# Sche.net
KiCad netlist of a schematic drawn in Altium Designer
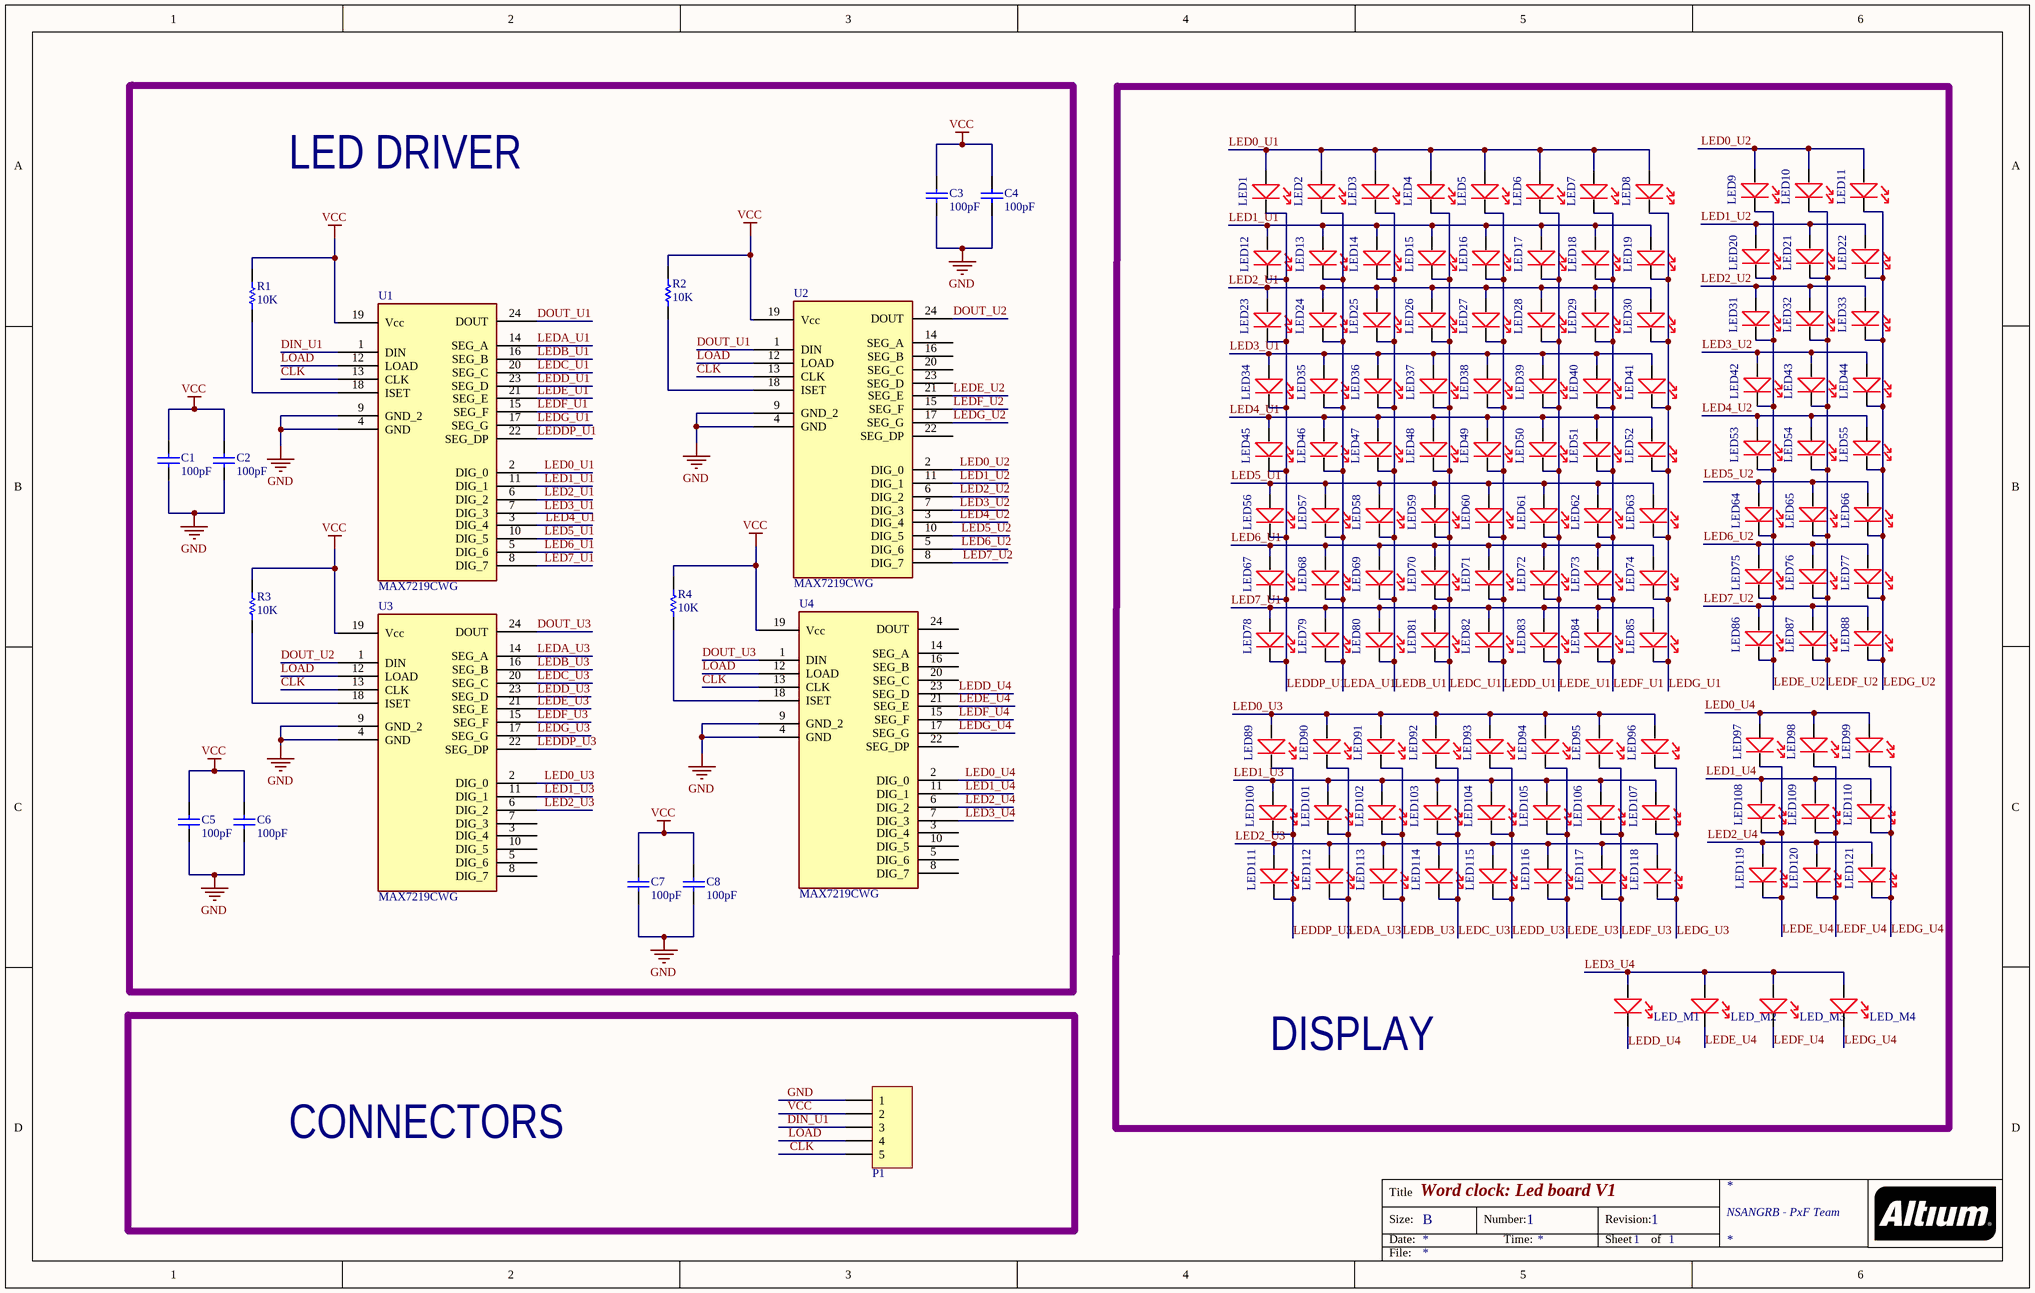
[diagram p0: Sche.SchDoc]

(export (version "E")
  (design (tool "Eeschema 10.0.6"))
  (components
    (comp (ref "C1")
      (value "100pF")
      (footprint "CAP-SM-0805")
      (description "Capacitor")
      (fields (field (name "Comment") "Cap Non-Pol SMD"))
      (libsource (lib "PIF_Library") (part "Cap Non-Pol SMD"))
    )
    (comp (ref "C2")
      (value "100pF")
      (footprint "CAP-SM-0805")
      (description "Capacitor")
      (fields (field (name "Comment") "Cap Non-Pol SMD"))
      (libsource (lib "PIF_Library") (part "Cap Non-Pol SMD"))
    )
    (comp (ref "C3")
      (value "100pF")
      (footprint "CAP-SM-0805")
      (description "Capacitor")
      (fields (field (name "Comment") "Cap Non-Pol SMD"))
      (libsource (lib "PIF_Library") (part "Cap Non-Pol SMD"))
    )
    (comp (ref "C4")
      (value "100pF")
      (footprint "CAP-SM-0805")
      (description "Capacitor")
      (fields (field (name "Comment") "Cap Non-Pol SMD"))
      (libsource (lib "PIF_Library") (part "Cap Non-Pol SMD"))
    )
    (comp (ref "C5")
      (value "100pF")
      (footprint "CAP-SM-0805")
      (description "Capacitor")
      (fields (field (name "Comment") "Cap Non-Pol SMD"))
      (libsource (lib "PIF_Library") (part "Cap Non-Pol SMD"))
    )
    (comp (ref "C6")
      (value "100pF")
      (footprint "CAP-SM-0805")
      (description "Capacitor")
      (fields (field (name "Comment") "Cap Non-Pol SMD"))
      (libsource (lib "PIF_Library") (part "Cap Non-Pol SMD"))
    )
    (comp (ref "C7")
      (value "100pF")
      (footprint "CAP-SM-0805")
      (description "Capacitor")
      (fields (field (name "Comment") "Cap Non-Pol SMD"))
      (libsource (lib "PIF_Library") (part "Cap Non-Pol SMD"))
    )
    (comp (ref "C8")
      (value "100pF")
      (footprint "CAP-SM-0805")
      (description "Capacitor")
      (fields (field (name "Comment") "Cap Non-Pol SMD"))
      (libsource (lib "PIF_Library") (part "Cap Non-Pol SMD"))
    )
    (comp (ref "LED1")
      (value "KA-3528EC")
      (footprint "DIOM3020X13N")
      (description "KINGBRIGHT         KA-3528EC             LED, Red, SMD, 2.4mm, 20 mA, 2 V, 627 nm")
      (fields (field (name "MANUFACTURER") "Kingbright"))
      (libsource (lib "WC_Lib") (part "LED_3528"))
    )
    (comp (ref "LED2")
      (value "KA-3528EC")
      (footprint "DIOM3020X13N")
      (description "KINGBRIGHT         KA-3528EC             LED, Red, SMD, 2.4mm, 20 mA, 2 V, 627 nm")
      (fields (field (name "MANUFACTURER") "Kingbright"))
      (libsource (lib "WC_Lib") (part "LED_3528"))
    )
    (comp (ref "LED3")
      (value "KA-3528EC")
      (footprint "DIOM3020X13N")
      (description "KINGBRIGHT         KA-3528EC             LED, Red, SMD, 2.4mm, 20 mA, 2 V, 627 nm")
      (fields (field (name "MANUFACTURER") "Kingbright"))
      (libsource (lib "WC_Lib") (part "LED_3528"))
    )
    (comp (ref "LED4")
      (value "KA-3528EC")
      (footprint "DIOM3020X13N")
      (description "KINGBRIGHT         KA-3528EC             LED, Red, SMD, 2.4mm, 20 mA, 2 V, 627 nm")
      (fields (field (name "MANUFACTURER") "Kingbright"))
      (libsource (lib "WC_Lib") (part "LED_3528"))
    )
    (comp (ref "LED5")
      (value "KA-3528EC")
      (footprint "DIOM3020X13N")
      (description "KINGBRIGHT         KA-3528EC             LED, Red, SMD, 2.4mm, 20 mA, 2 V, 627 nm")
      (fields (field (name "MANUFACTURER") "Kingbright"))
      (libsource (lib "WC_Lib") (part "LED_3528"))
    )
    (comp (ref "LED6")
      (value "KA-3528EC")
      (footprint "DIOM3020X13N")
      (description "KINGBRIGHT         KA-3528EC             LED, Red, SMD, 2.4mm, 20 mA, 2 V, 627 nm")
      (fields (field (name "MANUFACTURER") "Kingbright"))
      (libsource (lib "WC_Lib") (part "LED_3528"))
    )
    (comp (ref "LED7")
      (value "KA-3528EC")
      (footprint "DIOM3020X13N")
      (description "KINGBRIGHT         KA-3528EC             LED, Red, SMD, 2.4mm, 20 mA, 2 V, 627 nm")
      (fields (field (name "MANUFACTURER") "Kingbright"))
      (libsource (lib "WC_Lib") (part "LED_3528"))
    )
    (comp (ref "LED8")
      (value "KA-3528EC")
      (footprint "DIOM3020X13N")
      (description "KINGBRIGHT         KA-3528EC             LED, Red, SMD, 2.4mm, 20 mA, 2 V, 627 nm")
      (fields (field (name "MANUFACTURER") "Kingbright"))
      (libsource (lib "WC_Lib") (part "LED_3528"))
    )
    (comp (ref "LED9")
      (value "KA-3528EC")
      (footprint "DIOM3020X13N")
      (description "KINGBRIGHT         KA-3528EC             LED, Red, SMD, 2.4mm, 20 mA, 2 V, 627 nm")
      (fields (field (name "MANUFACTURER") "Kingbright"))
      (libsource (lib "WC_Lib") (part "LED_3528"))
    )
    (comp (ref "LED10")
      (value "KA-3528EC")
      (footprint "DIOM3020X13N")
      (description "KINGBRIGHT         KA-3528EC             LED, Red, SMD, 2.4mm, 20 mA, 2 V, 627 nm")
      (fields (field (name "MANUFACTURER") "Kingbright"))
      (libsource (lib "WC_Lib") (part "LED_3528"))
    )
    (comp (ref "LED11")
      (value "KA-3528EC")
      (footprint "DIOM3020X13N")
      (description "KINGBRIGHT         KA-3528EC             LED, Red, SMD, 2.4mm, 20 mA, 2 V, 627 nm")
      (fields (field (name "MANUFACTURER") "Kingbright"))
      (libsource (lib "WC_Lib") (part "LED_3528"))
    )
    (comp (ref "LED12")
      (value "KA-3528EC")
      (footprint "DIOM3020X13N")
      (description "KINGBRIGHT         KA-3528EC             LED, Red, SMD, 2.4mm, 20 mA, 2 V, 627 nm")
      (fields (field (name "MANUFACTURER") "Kingbright"))
      (libsource (lib "WC_Lib") (part "LED_3528"))
    )
    (comp (ref "LED13")
      (value "KA-3528EC")
      (footprint "DIOM3020X13N")
      (description "KINGBRIGHT         KA-3528EC             LED, Red, SMD, 2.4mm, 20 mA, 2 V, 627 nm")
      (fields (field (name "MANUFACTURER") "Kingbright"))
      (libsource (lib "WC_Lib") (part "LED_3528"))
    )
    (comp (ref "LED14")
      (value "KA-3528EC")
      (footprint "DIOM3020X13N")
      (description "KINGBRIGHT         KA-3528EC             LED, Red, SMD, 2.4mm, 20 mA, 2 V, 627 nm")
      (fields (field (name "MANUFACTURER") "Kingbright"))
      (libsource (lib "WC_Lib") (part "LED_3528"))
    )
    (comp (ref "LED15")
      (value "KA-3528EC")
      (footprint "DIOM3020X13N")
      (description "KINGBRIGHT         KA-3528EC             LED, Red, SMD, 2.4mm, 20 mA, 2 V, 627 nm")
      (fields (field (name "MANUFACTURER") "Kingbright"))
      (libsource (lib "WC_Lib") (part "LED_3528"))
    )
    (comp (ref "LED16")
      (value "KA-3528EC")
      (footprint "DIOM3020X13N")
      (description "KINGBRIGHT         KA-3528EC             LED, Red, SMD, 2.4mm, 20 mA, 2 V, 627 nm")
      (fields (field (name "MANUFACTURER") "Kingbright"))
      (libsource (lib "WC_Lib") (part "LED_3528"))
    )
    (comp (ref "LED17")
      (value "KA-3528EC")
      (footprint "DIOM3020X13N")
      (description "KINGBRIGHT         KA-3528EC             LED, Red, SMD, 2.4mm, 20 mA, 2 V, 627 nm")
      (fields (field (name "MANUFACTURER") "Kingbright"))
      (libsource (lib "WC_Lib") (part "LED_3528"))
    )
    (comp (ref "LED18")
      (value "KA-3528EC")
      (footprint "DIOM3020X13N")
      (description "KINGBRIGHT         KA-3528EC             LED, Red, SMD, 2.4mm, 20 mA, 2 V, 627 nm")
      (fields (field (name "MANUFACTURER") "Kingbright"))
      (libsource (lib "WC_Lib") (part "LED_3528"))
    )
    (comp (ref "LED19")
      (value "KA-3528EC")
      (footprint "DIOM3020X13N")
      (description "KINGBRIGHT         KA-3528EC             LED, Red, SMD, 2.4mm, 20 mA, 2 V, 627 nm")
      (fields (field (name "MANUFACTURER") "Kingbright"))
      (libsource (lib "WC_Lib") (part "LED_3528"))
    )
    (comp (ref "LED20")
      (value "KA-3528EC")
      (footprint "DIOM3020X13N")
      (description "KINGBRIGHT         KA-3528EC             LED, Red, SMD, 2.4mm, 20 mA, 2 V, 627 nm")
      (fields (field (name "MANUFACTURER") "Kingbright"))
      (libsource (lib "WC_Lib") (part "LED_3528"))
    )
    (comp (ref "LED21")
      (value "KA-3528EC")
      (footprint "DIOM3020X13N")
      (description "KINGBRIGHT         KA-3528EC             LED, Red, SMD, 2.4mm, 20 mA, 2 V, 627 nm")
      (fields (field (name "MANUFACTURER") "Kingbright"))
      (libsource (lib "WC_Lib") (part "LED_3528"))
    )
    (comp (ref "LED22")
      (value "KA-3528EC")
      (footprint "DIOM3020X13N")
      (description "KINGBRIGHT         KA-3528EC             LED, Red, SMD, 2.4mm, 20 mA, 2 V, 627 nm")
      (fields (field (name "MANUFACTURER") "Kingbright"))
      (libsource (lib "WC_Lib") (part "LED_3528"))
    )
    (comp (ref "LED23")
      (value "KA-3528EC")
      (footprint "DIOM3020X13N")
      (description "KINGBRIGHT         KA-3528EC             LED, Red, SMD, 2.4mm, 20 mA, 2 V, 627 nm")
      (fields (field (name "MANUFACTURER") "Kingbright"))
      (libsource (lib "WC_Lib") (part "LED_3528"))
    )
    (comp (ref "LED24")
      (value "KA-3528EC")
      (footprint "DIOM3020X13N")
      (description "KINGBRIGHT         KA-3528EC             LED, Red, SMD, 2.4mm, 20 mA, 2 V, 627 nm")
      (fields (field (name "MANUFACTURER") "Kingbright"))
      (libsource (lib "WC_Lib") (part "LED_3528"))
    )
    (comp (ref "LED25")
      (value "KA-3528EC")
      (footprint "DIOM3020X13N")
      (description "KINGBRIGHT         KA-3528EC             LED, Red, SMD, 2.4mm, 20 mA, 2 V, 627 nm")
      (fields (field (name "MANUFACTURER") "Kingbright"))
      (libsource (lib "WC_Lib") (part "LED_3528"))
    )
    (comp (ref "LED26")
      (value "KA-3528EC")
      (footprint "DIOM3020X13N")
      (description "KINGBRIGHT         KA-3528EC             LED, Red, SMD, 2.4mm, 20 mA, 2 V, 627 nm")
      (fields (field (name "MANUFACTURER") "Kingbright"))
      (libsource (lib "WC_Lib") (part "LED_3528"))
    )
    (comp (ref "LED27")
      (value "KA-3528EC")
      (footprint "DIOM3020X13N")
      (description "KINGBRIGHT         KA-3528EC             LED, Red, SMD, 2.4mm, 20 mA, 2 V, 627 nm")
      (fields (field (name "MANUFACTURER") "Kingbright"))
      (libsource (lib "WC_Lib") (part "LED_3528"))
    )
    (comp (ref "LED28")
      (value "KA-3528EC")
      (footprint "DIOM3020X13N")
      (description "KINGBRIGHT         KA-3528EC             LED, Red, SMD, 2.4mm, 20 mA, 2 V, 627 nm")
      (fields (field (name "MANUFACTURER") "Kingbright"))
      (libsource (lib "WC_Lib") (part "LED_3528"))
    )
    (comp (ref "LED29")
      (value "KA-3528EC")
      (footprint "DIOM3020X13N")
      (description "KINGBRIGHT         KA-3528EC             LED, Red, SMD, 2.4mm, 20 mA, 2 V, 627 nm")
      (fields (field (name "MANUFACTURER") "Kingbright"))
      (libsource (lib "WC_Lib") (part "LED_3528"))
    )
    (comp (ref "LED30")
      (value "KA-3528EC")
      (footprint "DIOM3020X13N")
      (description "KINGBRIGHT         KA-3528EC             LED, Red, SMD, 2.4mm, 20 mA, 2 V, 627 nm")
      (fields (field (name "MANUFACTURER") "Kingbright"))
      (libsource (lib "WC_Lib") (part "LED_3528"))
    )
    (comp (ref "LED31")
      (value "KA-3528EC")
      (footprint "DIOM3020X13N")
      (description "KINGBRIGHT         KA-3528EC             LED, Red, SMD, 2.4mm, 20 mA, 2 V, 627 nm")
      (fields (field (name "MANUFACTURER") "Kingbright"))
      (libsource (lib "WC_Lib") (part "LED_3528"))
    )
    (comp (ref "LED32")
      (value "KA-3528EC")
      (footprint "DIOM3020X13N")
      (description "KINGBRIGHT         KA-3528EC             LED, Red, SMD, 2.4mm, 20 mA, 2 V, 627 nm")
      (fields (field (name "MANUFACTURER") "Kingbright"))
      (libsource (lib "WC_Lib") (part "LED_3528"))
    )
    (comp (ref "LED33")
      (value "KA-3528EC")
      (footprint "DIOM3020X13N")
      (description "KINGBRIGHT         KA-3528EC             LED, Red, SMD, 2.4mm, 20 mA, 2 V, 627 nm")
      (fields (field (name "MANUFACTURER") "Kingbright"))
      (libsource (lib "WC_Lib") (part "LED_3528"))
    )
    (comp (ref "LED34")
      (value "KA-3528EC")
      (footprint "DIOM3020X13N")
      (description "KINGBRIGHT         KA-3528EC             LED, Red, SMD, 2.4mm, 20 mA, 2 V, 627 nm")
      (fields (field (name "MANUFACTURER") "Kingbright"))
      (libsource (lib "WC_Lib") (part "LED_3528"))
    )
    (comp (ref "LED35")
      (value "KA-3528EC")
      (footprint "DIOM3020X13N")
      (description "KINGBRIGHT         KA-3528EC             LED, Red, SMD, 2.4mm, 20 mA, 2 V, 627 nm")
      (fields (field (name "MANUFACTURER") "Kingbright"))
      (libsource (lib "WC_Lib") (part "LED_3528"))
    )
    (comp (ref "LED36")
      (value "KA-3528EC")
      (footprint "DIOM3020X13N")
      (description "KINGBRIGHT         KA-3528EC             LED, Red, SMD, 2.4mm, 20 mA, 2 V, 627 nm")
      (fields (field (name "MANUFACTURER") "Kingbright"))
      (libsource (lib "WC_Lib") (part "LED_3528"))
    )
    (comp (ref "LED37")
      (value "KA-3528EC")
      (footprint "DIOM3020X13N")
      (description "KINGBRIGHT         KA-3528EC             LED, Red, SMD, 2.4mm, 20 mA, 2 V, 627 nm")
      (fields (field (name "MANUFACTURER") "Kingbright"))
      (libsource (lib "WC_Lib") (part "LED_3528"))
    )
    (comp (ref "LED38")
      (value "KA-3528EC")
      (footprint "DIOM3020X13N")
      (description "KINGBRIGHT         KA-3528EC             LED, Red, SMD, 2.4mm, 20 mA, 2 V, 627 nm")
      (fields (field (name "MANUFACTURER") "Kingbright"))
      (libsource (lib "WC_Lib") (part "LED_3528"))
    )
    (comp (ref "LED39")
      (value "KA-3528EC")
      (footprint "DIOM3020X13N")
      (description "KINGBRIGHT         KA-3528EC             LED, Red, SMD, 2.4mm, 20 mA, 2 V, 627 nm")
      (fields (field (name "MANUFACTURER") "Kingbright"))
      (libsource (lib "WC_Lib") (part "LED_3528"))
    )
    (comp (ref "LED40")
      (value "KA-3528EC")
      (footprint "DIOM3020X13N")
      (description "KINGBRIGHT         KA-3528EC             LED, Red, SMD, 2.4mm, 20 mA, 2 V, 627 nm")
      (fields (field (name "MANUFACTURER") "Kingbright"))
      (libsource (lib "WC_Lib") (part "LED_3528"))
    )
    (comp (ref "LED41")
      (value "KA-3528EC")
      (footprint "DIOM3020X13N")
      (description "KINGBRIGHT         KA-3528EC             LED, Red, SMD, 2.4mm, 20 mA, 2 V, 627 nm")
      (fields (field (name "MANUFACTURER") "Kingbright"))
      (libsource (lib "WC_Lib") (part "LED_3528"))
    )
    (comp (ref "LED42")
      (value "KA-3528EC")
      (footprint "DIOM3020X13N")
      (description "KINGBRIGHT         KA-3528EC             LED, Red, SMD, 2.4mm, 20 mA, 2 V, 627 nm")
      (fields (field (name "MANUFACTURER") "Kingbright"))
      (libsource (lib "WC_Lib") (part "LED_3528"))
    )
    (comp (ref "LED43")
      (value "KA-3528EC")
      (footprint "DIOM3020X13N")
      (description "KINGBRIGHT         KA-3528EC             LED, Red, SMD, 2.4mm, 20 mA, 2 V, 627 nm")
      (fields (field (name "MANUFACTURER") "Kingbright"))
      (libsource (lib "WC_Lib") (part "LED_3528"))
    )
    (comp (ref "LED44")
      (value "KA-3528EC")
      (footprint "DIOM3020X13N")
      (description "KINGBRIGHT         KA-3528EC             LED, Red, SMD, 2.4mm, 20 mA, 2 V, 627 nm")
      (fields (field (name "MANUFACTURER") "Kingbright"))
      (libsource (lib "WC_Lib") (part "LED_3528"))
    )
    (comp (ref "LED45")
      (value "KA-3528EC")
      (footprint "DIOM3020X13N")
      (description "KINGBRIGHT         KA-3528EC             LED, Red, SMD, 2.4mm, 20 mA, 2 V, 627 nm")
      (fields (field (name "MANUFACTURER") "Kingbright"))
      (libsource (lib "WC_Lib") (part "LED_3528"))
    )
    (comp (ref "LED46")
      (value "KA-3528EC")
      (footprint "DIOM3020X13N")
      (description "KINGBRIGHT         KA-3528EC             LED, Red, SMD, 2.4mm, 20 mA, 2 V, 627 nm")
      (fields (field (name "MANUFACTURER") "Kingbright"))
      (libsource (lib "WC_Lib") (part "LED_3528"))
    )
    (comp (ref "LED47")
      (value "KA-3528EC")
      (footprint "DIOM3020X13N")
      (description "KINGBRIGHT         KA-3528EC             LED, Red, SMD, 2.4mm, 20 mA, 2 V, 627 nm")
      (fields (field (name "MANUFACTURER") "Kingbright"))
      (libsource (lib "WC_Lib") (part "LED_3528"))
    )
    (comp (ref "LED48")
      (value "KA-3528EC")
      (footprint "DIOM3020X13N")
      (description "KINGBRIGHT         KA-3528EC             LED, Red, SMD, 2.4mm, 20 mA, 2 V, 627 nm")
      (fields (field (name "MANUFACTURER") "Kingbright"))
      (libsource (lib "WC_Lib") (part "LED_3528"))
    )
    (comp (ref "LED49")
      (value "KA-3528EC")
      (footprint "DIOM3020X13N")
      (description "KINGBRIGHT         KA-3528EC             LED, Red, SMD, 2.4mm, 20 mA, 2 V, 627 nm")
      (fields (field (name "MANUFACTURER") "Kingbright"))
      (libsource (lib "WC_Lib") (part "LED_3528"))
    )
    (comp (ref "LED50")
      (value "KA-3528EC")
      (footprint "DIOM3020X13N")
      (description "KINGBRIGHT         KA-3528EC             LED, Red, SMD, 2.4mm, 20 mA, 2 V, 627 nm")
      (fields (field (name "MANUFACTURER") "Kingbright"))
      (libsource (lib "WC_Lib") (part "LED_3528"))
    )
    (comp (ref "LED51")
      (value "KA-3528EC")
      (footprint "DIOM3020X13N")
      (description "KINGBRIGHT         KA-3528EC             LED, Red, SMD, 2.4mm, 20 mA, 2 V, 627 nm")
      (fields (field (name "MANUFACTURER") "Kingbright"))
      (libsource (lib "WC_Lib") (part "LED_3528"))
    )
    (comp (ref "LED52")
      (value "KA-3528EC")
      (footprint "DIOM3020X13N")
      (description "KINGBRIGHT         KA-3528EC             LED, Red, SMD, 2.4mm, 20 mA, 2 V, 627 nm")
      (fields (field (name "MANUFACTURER") "Kingbright"))
      (libsource (lib "WC_Lib") (part "LED_3528"))
    )
    (comp (ref "LED53")
      (value "KA-3528EC")
      (footprint "DIOM3020X13N")
      (description "KINGBRIGHT         KA-3528EC             LED, Red, SMD, 2.4mm, 20 mA, 2 V, 627 nm")
      (fields (field (name "MANUFACTURER") "Kingbright"))
      (libsource (lib "WC_Lib") (part "LED_3528"))
    )
    (comp (ref "LED54")
      (value "KA-3528EC")
      (footprint "DIOM3020X13N")
      (description "KINGBRIGHT         KA-3528EC             LED, Red, SMD, 2.4mm, 20 mA, 2 V, 627 nm")
      (fields (field (name "MANUFACTURER") "Kingbright"))
      (libsource (lib "WC_Lib") (part "LED_3528"))
    )
    (comp (ref "LED55")
      (value "KA-3528EC")
      (footprint "DIOM3020X13N")
      (description "KINGBRIGHT         KA-3528EC             LED, Red, SMD, 2.4mm, 20 mA, 2 V, 627 nm")
      (fields (field (name "MANUFACTURER") "Kingbright"))
      (libsource (lib "WC_Lib") (part "LED_3528"))
    )
    (comp (ref "LED56")
      (value "KA-3528EC")
      (footprint "DIOM3020X13N")
      (description "KINGBRIGHT         KA-3528EC             LED, Red, SMD, 2.4mm, 20 mA, 2 V, 627 nm")
      (fields (field (name "MANUFACTURER") "Kingbright"))
      (libsource (lib "WC_Lib") (part "LED_3528"))
    )
    (comp (ref "LED57")
      (value "KA-3528EC")
      (footprint "DIOM3020X13N")
      (description "KINGBRIGHT         KA-3528EC             LED, Red, SMD, 2.4mm, 20 mA, 2 V, 627 nm")
      (fields (field (name "MANUFACTURER") "Kingbright"))
      (libsource (lib "WC_Lib") (part "LED_3528"))
    )
    (comp (ref "LED58")
      (value "KA-3528EC")
      (footprint "DIOM3020X13N")
      (description "KINGBRIGHT         KA-3528EC             LED, Red, SMD, 2.4mm, 20 mA, 2 V, 627 nm")
      (fields (field (name "MANUFACTURER") "Kingbright"))
      (libsource (lib "WC_Lib") (part "LED_3528"))
    )
    (comp (ref "LED59")
      (value "KA-3528EC")
      (footprint "DIOM3020X13N")
      (description "KINGBRIGHT         KA-3528EC             LED, Red, SMD, 2.4mm, 20 mA, 2 V, 627 nm")
      (fields (field (name "MANUFACTURER") "Kingbright"))
      (libsource (lib "WC_Lib") (part "LED_3528"))
    )
    (comp (ref "LED60")
      (value "KA-3528EC")
      (footprint "DIOM3020X13N")
      (description "KINGBRIGHT         KA-3528EC             LED, Red, SMD, 2.4mm, 20 mA, 2 V, 627 nm")
      (fields (field (name "MANUFACTURER") "Kingbright"))
      (libsource (lib "WC_Lib") (part "LED_3528"))
    )
    (comp (ref "LED61")
      (value "KA-3528EC")
      (footprint "DIOM3020X13N")
      (description "KINGBRIGHT         KA-3528EC             LED, Red, SMD, 2.4mm, 20 mA, 2 V, 627 nm")
      (fields (field (name "MANUFACTURER") "Kingbright"))
      (libsource (lib "WC_Lib") (part "LED_3528"))
    )
    (comp (ref "LED62")
      (value "KA-3528EC")
      (footprint "DIOM3020X13N")
      (description "KINGBRIGHT         KA-3528EC             LED, Red, SMD, 2.4mm, 20 mA, 2 V, 627 nm")
      (fields (field (name "MANUFACTURER") "Kingbright"))
      (libsource (lib "WC_Lib") (part "LED_3528"))
    )
    (comp (ref "LED63")
      (value "KA-3528EC")
      (footprint "DIOM3020X13N")
      (description "KINGBRIGHT         KA-3528EC             LED, Red, SMD, 2.4mm, 20 mA, 2 V, 627 nm")
      (fields (field (name "MANUFACTURER") "Kingbright"))
      (libsource (lib "WC_Lib") (part "LED_3528"))
    )
    (comp (ref "LED64")
      (value "KA-3528EC")
      (footprint "DIOM3020X13N")
      (description "KINGBRIGHT         KA-3528EC             LED, Red, SMD, 2.4mm, 20 mA, 2 V, 627 nm")
      (fields (field (name "MANUFACTURER") "Kingbright"))
      (libsource (lib "WC_Lib") (part "LED_3528"))
    )
    (comp (ref "LED65")
      (value "KA-3528EC")
      (footprint "DIOM3020X13N")
      (description "KINGBRIGHT         KA-3528EC             LED, Red, SMD, 2.4mm, 20 mA, 2 V, 627 nm")
      (fields (field (name "MANUFACTURER") "Kingbright"))
      (libsource (lib "WC_Lib") (part "LED_3528"))
    )
    (comp (ref "LED66")
      (value "KA-3528EC")
      (footprint "DIOM3020X13N")
      (description "KINGBRIGHT         KA-3528EC             LED, Red, SMD, 2.4mm, 20 mA, 2 V, 627 nm")
      (fields (field (name "MANUFACTURER") "Kingbright"))
      (libsource (lib "WC_Lib") (part "LED_3528"))
    )
    (comp (ref "LED67")
      (value "KA-3528EC")
      (footprint "DIOM3020X13N")
      (description "KINGBRIGHT         KA-3528EC             LED, Red, SMD, 2.4mm, 20 mA, 2 V, 627 nm")
      (fields (field (name "MANUFACTURER") "Kingbright"))
      (libsource (lib "WC_Lib") (part "LED_3528"))
    )
    (comp (ref "LED68")
      (value "KA-3528EC")
      (footprint "DIOM3020X13N")
      (description "KINGBRIGHT         KA-3528EC             LED, Red, SMD, 2.4mm, 20 mA, 2 V, 627 nm")
      (fields (field (name "MANUFACTURER") "Kingbright"))
      (libsource (lib "WC_Lib") (part "LED_3528"))
    )
    (comp (ref "LED69")
      (value "KA-3528EC")
      (footprint "DIOM3020X13N")
      (description "KINGBRIGHT         KA-3528EC             LED, Red, SMD, 2.4mm, 20 mA, 2 V, 627 nm")
      (fields (field (name "MANUFACTURER") "Kingbright"))
      (libsource (lib "WC_Lib") (part "LED_3528"))
    )
    (comp (ref "LED70")
      (value "KA-3528EC")
      (footprint "DIOM3020X13N")
      (description "KINGBRIGHT         KA-3528EC             LED, Red, SMD, 2.4mm, 20 mA, 2 V, 627 nm")
      (fields (field (name "MANUFACTURER") "Kingbright"))
      (libsource (lib "WC_Lib") (part "LED_3528"))
    )
    (comp (ref "LED71")
      (value "KA-3528EC")
      (footprint "DIOM3020X13N")
      (description "KINGBRIGHT         KA-3528EC             LED, Red, SMD, 2.4mm, 20 mA, 2 V, 627 nm")
      (fields (field (name "MANUFACTURER") "Kingbright"))
      (libsource (lib "WC_Lib") (part "LED_3528"))
    )
    (comp (ref "LED72")
      (value "KA-3528EC")
      (footprint "DIOM3020X13N")
      (description "KINGBRIGHT         KA-3528EC             LED, Red, SMD, 2.4mm, 20 mA, 2 V, 627 nm")
      (fields (field (name "MANUFACTURER") "Kingbright"))
      (libsource (lib "WC_Lib") (part "LED_3528"))
    )
    (comp (ref "LED73")
      (value "KA-3528EC")
      (footprint "DIOM3020X13N")
      (description "KINGBRIGHT         KA-3528EC             LED, Red, SMD, 2.4mm, 20 mA, 2 V, 627 nm")
      (fields (field (name "MANUFACTURER") "Kingbright"))
      (libsource (lib "WC_Lib") (part "LED_3528"))
    )
    (comp (ref "LED74")
      (value "KA-3528EC")
      (footprint "DIOM3020X13N")
      (description "KINGBRIGHT         KA-3528EC             LED, Red, SMD, 2.4mm, 20 mA, 2 V, 627 nm")
      (fields (field (name "MANUFACTURER") "Kingbright"))
      (libsource (lib "WC_Lib") (part "LED_3528"))
    )
    (comp (ref "LED75")
      (value "KA-3528EC")
      (footprint "DIOM3020X13N")
      (description "KINGBRIGHT         KA-3528EC             LED, Red, SMD, 2.4mm, 20 mA, 2 V, 627 nm")
      (fields (field (name "MANUFACTURER") "Kingbright"))
      (libsource (lib "WC_Lib") (part "LED_3528"))
    )
    (comp (ref "LED76")
      (value "KA-3528EC")
      (footprint "DIOM3020X13N")
      (description "KINGBRIGHT         KA-3528EC             LED, Red, SMD, 2.4mm, 20 mA, 2 V, 627 nm")
      (fields (field (name "MANUFACTURER") "Kingbright"))
      (libsource (lib "WC_Lib") (part "LED_3528"))
    )
    (comp (ref "LED77")
      (value "KA-3528EC")
      (footprint "DIOM3020X13N")
      (description "KINGBRIGHT         KA-3528EC             LED, Red, SMD, 2.4mm, 20 mA, 2 V, 627 nm")
      (fields (field (name "MANUFACTURER") "Kingbright"))
      (libsource (lib "WC_Lib") (part "LED_3528"))
    )
    (comp (ref "LED78")
      (value "KA-3528EC")
      (footprint "DIOM3020X13N")
      (description "KINGBRIGHT         KA-3528EC             LED, Red, SMD, 2.4mm, 20 mA, 2 V, 627 nm")
      (fields (field (name "MANUFACTURER") "Kingbright"))
      (libsource (lib "WC_Lib") (part "LED_3528"))
    )
    (comp (ref "LED79")
      (value "KA-3528EC")
      (footprint "DIOM3020X13N")
      (description "KINGBRIGHT         KA-3528EC             LED, Red, SMD, 2.4mm, 20 mA, 2 V, 627 nm")
      (fields (field (name "MANUFACTURER") "Kingbright"))
      (libsource (lib "WC_Lib") (part "LED_3528"))
    )
    (comp (ref "LED80")
      (value "KA-3528EC")
      (footprint "DIOM3020X13N")
      (description "KINGBRIGHT         KA-3528EC             LED, Red, SMD, 2.4mm, 20 mA, 2 V, 627 nm")
      (fields (field (name "MANUFACTURER") "Kingbright"))
      (libsource (lib "WC_Lib") (part "LED_3528"))
    )
    (comp (ref "LED81")
      (value "KA-3528EC")
      (footprint "DIOM3020X13N")
      (description "KINGBRIGHT         KA-3528EC             LED, Red, SMD, 2.4mm, 20 mA, 2 V, 627 nm")
      (fields (field (name "MANUFACTURER") "Kingbright"))
      (libsource (lib "WC_Lib") (part "LED_3528"))
    )
    (comp (ref "LED82")
      (value "KA-3528EC")
      (footprint "DIOM3020X13N")
      (description "KINGBRIGHT         KA-3528EC             LED, Red, SMD, 2.4mm, 20 mA, 2 V, 627 nm")
      (fields (field (name "MANUFACTURER") "Kingbright"))
      (libsource (lib "WC_Lib") (part "LED_3528"))
    )
    (comp (ref "LED83")
      (value "KA-3528EC")
      (footprint "DIOM3020X13N")
      (description "KINGBRIGHT         KA-3528EC             LED, Red, SMD, 2.4mm, 20 mA, 2 V, 627 nm")
      (fields (field (name "MANUFACTURER") "Kingbright"))
      (libsource (lib "WC_Lib") (part "LED_3528"))
    )
    (comp (ref "LED84")
      (value "KA-3528EC")
      (footprint "DIOM3020X13N")
      (description "KINGBRIGHT         KA-3528EC             LED, Red, SMD, 2.4mm, 20 mA, 2 V, 627 nm")
      (fields (field (name "MANUFACTURER") "Kingbright"))
      (libsource (lib "WC_Lib") (part "LED_3528"))
    )
    (comp (ref "LED85")
      (value "KA-3528EC")
      (footprint "DIOM3020X13N")
      (description "KINGBRIGHT         KA-3528EC             LED, Red, SMD, 2.4mm, 20 mA, 2 V, 627 nm")
      (fields (field (name "MANUFACTURER") "Kingbright"))
      (libsource (lib "WC_Lib") (part "LED_3528"))
    )
    (comp (ref "LED86")
      (value "KA-3528EC")
      (footprint "DIOM3020X13N")
      (description "KINGBRIGHT         KA-3528EC             LED, Red, SMD, 2.4mm, 20 mA, 2 V, 627 nm")
      (fields (field (name "MANUFACTURER") "Kingbright"))
      (libsource (lib "WC_Lib") (part "LED_3528"))
    )
    (comp (ref "LED87")
      (value "KA-3528EC")
      (footprint "DIOM3020X13N")
      (description "KINGBRIGHT         KA-3528EC             LED, Red, SMD, 2.4mm, 20 mA, 2 V, 627 nm")
      (fields (field (name "MANUFACTURER") "Kingbright"))
      (libsource (lib "WC_Lib") (part "LED_3528"))
    )
    (comp (ref "LED88")
      (value "KA-3528EC")
      (footprint "DIOM3020X13N")
      (description "KINGBRIGHT         KA-3528EC             LED, Red, SMD, 2.4mm, 20 mA, 2 V, 627 nm")
      (fields (field (name "MANUFACTURER") "Kingbright"))
      (libsource (lib "WC_Lib") (part "LED_3528"))
    )
    (comp (ref "LED89")
      (value "KA-3528EC")
      (footprint "DIOM3020X13N")
      (description "KINGBRIGHT         KA-3528EC             LED, Red, SMD, 2.4mm, 20 mA, 2 V, 627 nm")
      (fields (field (name "MANUFACTURER") "Kingbright"))
      (libsource (lib "WC_Lib") (part "LED_3528"))
    )
    (comp (ref "LED90")
      (value "KA-3528EC")
      (footprint "DIOM3020X13N")
      (description "KINGBRIGHT         KA-3528EC             LED, Red, SMD, 2.4mm, 20 mA, 2 V, 627 nm")
      (fields (field (name "MANUFACTURER") "Kingbright"))
      (libsource (lib "WC_Lib") (part "LED_3528"))
    )
    (comp (ref "LED91")
      (value "KA-3528EC")
      (footprint "DIOM3020X13N")
      (description "KINGBRIGHT         KA-3528EC             LED, Red, SMD, 2.4mm, 20 mA, 2 V, 627 nm")
      (fields (field (name "MANUFACTURER") "Kingbright"))
      (libsource (lib "WC_Lib") (part "LED_3528"))
    )
    (comp (ref "LED92")
      (value "KA-3528EC")
      (footprint "DIOM3020X13N")
      (description "KINGBRIGHT         KA-3528EC             LED, Red, SMD, 2.4mm, 20 mA, 2 V, 627 nm")
      (fields (field (name "MANUFACTURER") "Kingbright"))
      (libsource (lib "WC_Lib") (part "LED_3528"))
    )
    (comp (ref "LED93")
      (value "KA-3528EC")
      (footprint "DIOM3020X13N")
      (description "KINGBRIGHT         KA-3528EC             LED, Red, SMD, 2.4mm, 20 mA, 2 V, 627 nm")
      (fields (field (name "MANUFACTURER") "Kingbright"))
      (libsource (lib "WC_Lib") (part "LED_3528"))
    )
    (comp (ref "LED94")
      (value "KA-3528EC")
      (footprint "DIOM3020X13N")
      (description "KINGBRIGHT         KA-3528EC             LED, Red, SMD, 2.4mm, 20 mA, 2 V, 627 nm")
      (fields (field (name "MANUFACTURER") "Kingbright"))
      (libsource (lib "WC_Lib") (part "LED_3528"))
    )
    (comp (ref "LED95")
      (value "KA-3528EC")
      (footprint "DIOM3020X13N")
      (description "KINGBRIGHT         KA-3528EC             LED, Red, SMD, 2.4mm, 20 mA, 2 V, 627 nm")
      (fields (field (name "MANUFACTURER") "Kingbright"))
      (libsource (lib "WC_Lib") (part "LED_3528"))
    )
    (comp (ref "LED96")
      (value "KA-3528EC")
      (footprint "DIOM3020X13N")
      (description "KINGBRIGHT         KA-3528EC             LED, Red, SMD, 2.4mm, 20 mA, 2 V, 627 nm")
      (fields (field (name "MANUFACTURER") "Kingbright"))
      (libsource (lib "WC_Lib") (part "LED_3528"))
    )
    (comp (ref "LED97")
      (value "KA-3528EC")
      (footprint "DIOM3020X13N")
      (description "KINGBRIGHT         KA-3528EC             LED, Red, SMD, 2.4mm, 20 mA, 2 V, 627 nm")
      (fields (field (name "MANUFACTURER") "Kingbright"))
      (libsource (lib "WC_Lib") (part "LED_3528"))
    )
    (comp (ref "LED98")
      (value "KA-3528EC")
      (footprint "DIOM3020X13N")
      (description "KINGBRIGHT         KA-3528EC             LED, Red, SMD, 2.4mm, 20 mA, 2 V, 627 nm")
      (fields (field (name "MANUFACTURER") "Kingbright"))
      (libsource (lib "WC_Lib") (part "LED_3528"))
    )
    (comp (ref "LED99")
      (value "KA-3528EC")
      (footprint "DIOM3020X13N")
      (description "KINGBRIGHT         KA-3528EC             LED, Red, SMD, 2.4mm, 20 mA, 2 V, 627 nm")
      (fields (field (name "MANUFACTURER") "Kingbright"))
      (libsource (lib "WC_Lib") (part "LED_3528"))
    )
    (comp (ref "LED100")
      (value "KA-3528EC")
      (footprint "DIOM3020X13N")
      (description "KINGBRIGHT         KA-3528EC             LED, Red, SMD, 2.4mm, 20 mA, 2 V, 627 nm")
      (fields (field (name "MANUFACTURER") "Kingbright"))
      (libsource (lib "WC_Lib") (part "LED_3528"))
    )
    (comp (ref "LED101")
      (value "KA-3528EC")
      (footprint "DIOM3020X13N")
      (description "KINGBRIGHT         KA-3528EC             LED, Red, SMD, 2.4mm, 20 mA, 2 V, 627 nm")
      (fields (field (name "MANUFACTURER") "Kingbright"))
      (libsource (lib "WC_Lib") (part "LED_3528"))
    )
    (comp (ref "LED102")
      (value "KA-3528EC")
      (footprint "DIOM3020X13N")
      (description "KINGBRIGHT         KA-3528EC             LED, Red, SMD, 2.4mm, 20 mA, 2 V, 627 nm")
      (fields (field (name "MANUFACTURER") "Kingbright"))
      (libsource (lib "WC_Lib") (part "LED_3528"))
    )
    (comp (ref "LED103")
      (value "KA-3528EC")
      (footprint "DIOM3020X13N")
      (description "KINGBRIGHT         KA-3528EC             LED, Red, SMD, 2.4mm, 20 mA, 2 V, 627 nm")
      (fields (field (name "MANUFACTURER") "Kingbright"))
      (libsource (lib "WC_Lib") (part "LED_3528"))
    )
    (comp (ref "LED104")
      (value "KA-3528EC")
      (footprint "DIOM3020X13N")
      (description "KINGBRIGHT         KA-3528EC             LED, Red, SMD, 2.4mm, 20 mA, 2 V, 627 nm")
      (fields (field (name "MANUFACTURER") "Kingbright"))
      (libsource (lib "WC_Lib") (part "LED_3528"))
    )
    (comp (ref "LED105")
      (value "KA-3528EC")
      (footprint "DIOM3020X13N")
      (description "KINGBRIGHT         KA-3528EC             LED, Red, SMD, 2.4mm, 20 mA, 2 V, 627 nm")
      (fields (field (name "MANUFACTURER") "Kingbright"))
      (libsource (lib "WC_Lib") (part "LED_3528"))
    )
    (comp (ref "LED106")
      (value "KA-3528EC")
      (footprint "DIOM3020X13N")
      (description "KINGBRIGHT         KA-3528EC             LED, Red, SMD, 2.4mm, 20 mA, 2 V, 627 nm")
      (fields (field (name "MANUFACTURER") "Kingbright"))
      (libsource (lib "WC_Lib") (part "LED_3528"))
    )
    (comp (ref "LED107")
      (value "KA-3528EC")
      (footprint "DIOM3020X13N")
      (description "KINGBRIGHT         KA-3528EC             LED, Red, SMD, 2.4mm, 20 mA, 2 V, 627 nm")
      (fields (field (name "MANUFACTURER") "Kingbright"))
      (libsource (lib "WC_Lib") (part "LED_3528"))
    )
    (comp (ref "LED108")
      (value "KA-3528EC")
      (footprint "DIOM3020X13N")
      (description "KINGBRIGHT         KA-3528EC             LED, Red, SMD, 2.4mm, 20 mA, 2 V, 627 nm")
      (fields (field (name "MANUFACTURER") "Kingbright"))
      (libsource (lib "WC_Lib") (part "LED_3528"))
    )
    (comp (ref "LED109")
      (value "KA-3528EC")
      (footprint "DIOM3020X13N")
      (description "KINGBRIGHT         KA-3528EC             LED, Red, SMD, 2.4mm, 20 mA, 2 V, 627 nm")
      (fields (field (name "MANUFACTURER") "Kingbright"))
      (libsource (lib "WC_Lib") (part "LED_3528"))
    )
    (comp (ref "LED110")
      (value "KA-3528EC")
      (footprint "DIOM3020X13N")
      (description "KINGBRIGHT         KA-3528EC             LED, Red, SMD, 2.4mm, 20 mA, 2 V, 627 nm")
      (fields (field (name "MANUFACTURER") "Kingbright"))
      (libsource (lib "WC_Lib") (part "LED_3528"))
    )
    (comp (ref "LED111")
      (value "KA-3528EC")
      (footprint "DIOM3020X13N")
      (description "KINGBRIGHT         KA-3528EC             LED, Red, SMD, 2.4mm, 20 mA, 2 V, 627 nm")
      (fields (field (name "MANUFACTURER") "Kingbright"))
      (libsource (lib "WC_Lib") (part "LED_3528"))
    )
    (comp (ref "LED112")
      (value "KA-3528EC")
      (footprint "DIOM3020X13N")
      (description "KINGBRIGHT         KA-3528EC             LED, Red, SMD, 2.4mm, 20 mA, 2 V, 627 nm")
      (fields (field (name "MANUFACTURER") "Kingbright"))
      (libsource (lib "WC_Lib") (part "LED_3528"))
    )
    (comp (ref "LED113")
      (value "KA-3528EC")
      (footprint "DIOM3020X13N")
      (description "KINGBRIGHT         KA-3528EC             LED, Red, SMD, 2.4mm, 20 mA, 2 V, 627 nm")
      (fields (field (name "MANUFACTURER") "Kingbright"))
      (libsource (lib "WC_Lib") (part "LED_3528"))
    )
    (comp (ref "LED114")
      (value "KA-3528EC")
      (footprint "DIOM3020X13N")
      (description "KINGBRIGHT         KA-3528EC             LED, Red, SMD, 2.4mm, 20 mA, 2 V, 627 nm")
      (fields (field (name "MANUFACTURER") "Kingbright"))
      (libsource (lib "WC_Lib") (part "LED_3528"))
    )
    (comp (ref "LED115")
      (value "KA-3528EC")
      (footprint "DIOM3020X13N")
      (description "KINGBRIGHT         KA-3528EC             LED, Red, SMD, 2.4mm, 20 mA, 2 V, 627 nm")
      (fields (field (name "MANUFACTURER") "Kingbright"))
      (libsource (lib "WC_Lib") (part "LED_3528"))
    )
    (comp (ref "LED116")
      (value "KA-3528EC")
      (footprint "DIOM3020X13N")
      (description "KINGBRIGHT         KA-3528EC             LED, Red, SMD, 2.4mm, 20 mA, 2 V, 627 nm")
      (fields (field (name "MANUFACTURER") "Kingbright"))
      (libsource (lib "WC_Lib") (part "LED_3528"))
    )
    (comp (ref "LED117")
      (value "KA-3528EC")
      (footprint "DIOM3020X13N")
      (description "KINGBRIGHT         KA-3528EC             LED, Red, SMD, 2.4mm, 20 mA, 2 V, 627 nm")
      (fields (field (name "MANUFACTURER") "Kingbright"))
      (libsource (lib "WC_Lib") (part "LED_3528"))
    )
    (comp (ref "LED118")
      (value "KA-3528EC")
      (footprint "DIOM3020X13N")
      (description "KINGBRIGHT         KA-3528EC             LED, Red, SMD, 2.4mm, 20 mA, 2 V, 627 nm")
      (fields (field (name "MANUFACTURER") "Kingbright"))
      (libsource (lib "WC_Lib") (part "LED_3528"))
    )
    (comp (ref "LED119")
      (value "KA-3528EC")
      (footprint "DIOM3020X13N")
      (description "KINGBRIGHT         KA-3528EC             LED, Red, SMD, 2.4mm, 20 mA, 2 V, 627 nm")
      (fields (field (name "MANUFACTURER") "Kingbright"))
      (libsource (lib "WC_Lib") (part "LED_3528"))
    )
    (comp (ref "LED120")
      (value "KA-3528EC")
      (footprint "DIOM3020X13N")
      (description "KINGBRIGHT         KA-3528EC             LED, Red, SMD, 2.4mm, 20 mA, 2 V, 627 nm")
      (fields (field (name "MANUFACTURER") "Kingbright"))
      (libsource (lib "WC_Lib") (part "LED_3528"))
    )
    (comp (ref "LED121")
      (value "KA-3528EC")
      (footprint "DIOM3020X13N")
      (description "KINGBRIGHT         KA-3528EC             LED, Red, SMD, 2.4mm, 20 mA, 2 V, 627 nm")
      (fields (field (name "MANUFACTURER") "Kingbright"))
      (libsource (lib "WC_Lib") (part "LED_3528"))
    )
    (comp (ref "LED_M1")
      (value "KA-3528EC")
      (footprint "DIOM3020X13N")
      (description "KINGBRIGHT         KA-3528EC             LED, Red, SMD, 2.4mm, 20 mA, 2 V, 627 nm")
      (fields (field (name "MANUFACTURER") "Kingbright"))
      (libsource (lib "WC_Lib") (part "LED_3528"))
    )
    (comp (ref "LED_M2")
      (value "KA-3528EC")
      (footprint "DIOM3020X13N")
      (description "KINGBRIGHT         KA-3528EC             LED, Red, SMD, 2.4mm, 20 mA, 2 V, 627 nm")
      (fields (field (name "MANUFACTURER") "Kingbright"))
      (libsource (lib "WC_Lib") (part "LED_3528"))
    )
    (comp (ref "LED_M3")
      (value "KA-3528EC")
      (footprint "DIOM3020X13N")
      (description "KINGBRIGHT         KA-3528EC             LED, Red, SMD, 2.4mm, 20 mA, 2 V, 627 nm")
      (fields (field (name "MANUFACTURER") "Kingbright"))
      (libsource (lib "WC_Lib") (part "LED_3528"))
    )
    (comp (ref "LED_M4")
      (value "KA-3528EC")
      (footprint "DIOM3020X13N")
      (description "KINGBRIGHT         KA-3528EC             LED, Red, SMD, 2.4mm, 20 mA, 2 V, 627 nm")
      (fields (field (name "MANUFACTURER") "Kingbright"))
      (libsource (lib "WC_Lib") (part "LED_3528"))
    )
    (comp (ref "P1")
      (value "Header 5")
      (footprint "JP5")
      (description "Header, 5-Pin")
      (fields (field (name "PUBLISHER") "Altium Limited"))
      (libsource (lib "PIF_Library") (part "Header 5"))
    )
    (comp (ref "R1")
      (value "10K")
      (footprint "RES-SM-0805")
      (description "Resistor")
      (fields (field (name "Comment") "RESISTOR SMD"))
      (libsource (lib "PIF_Library") (part "RESISTOR SMD"))
    )
    (comp (ref "R2")
      (value "10K")
      (footprint "RES-SM-0805")
      (description "Resistor")
      (fields (field (name "Comment") "RESISTOR SMD"))
      (libsource (lib "PIF_Library") (part "RESISTOR SMD"))
    )
    (comp (ref "R3")
      (value "10K")
      (footprint "RES-SM-0805")
      (description "Resistor")
      (fields (field (name "Comment") "RESISTOR SMD"))
      (libsource (lib "PIF_Library") (part "RESISTOR SMD"))
    )
    (comp (ref "R4")
      (value "10K")
      (footprint "RES-SM-0805")
      (description "Resistor")
      (fields (field (name "Comment") "RESISTOR SMD"))
      (libsource (lib "PIF_Library") (part "RESISTOR SMD"))
    )
    (comp (ref "U1")
      (value "MAX7219CWG")
      (footprint "SOIC127P1030X265-24N")
      (description "IC DRIVER LED DISP 8DGT 24-SOIC")
      (fields (field (name "MANUFACTURER") "Maxim"))
      (libsource (lib "WC_Lib") (part "MAX7219CWG"))
    )
    (comp (ref "U2")
      (value "MAX7219CWG")
      (footprint "SOIC127P1030X265-24N")
      (description "IC DRIVER LED DISP 8DGT 24-SOIC")
      (fields (field (name "MANUFACTURER") "Maxim"))
      (libsource (lib "WC_Lib") (part "MAX7219CWG"))
    )
    (comp (ref "U3")
      (value "MAX7219CWG")
      (footprint "SOIC127P1030X265-24N")
      (description "IC DRIVER LED DISP 8DGT 24-SOIC")
      (fields (field (name "MANUFACTURER") "Maxim"))
      (libsource (lib "WC_Lib") (part "MAX7219CWG"))
    )
    (comp (ref "U4")
      (value "MAX7219CWG")
      (footprint "SOIC127P1030X265-24N")
      (description "IC DRIVER LED DISP 8DGT 24-SOIC")
      (fields (field (name "MANUFACTURER") "Maxim"))
      (libsource (lib "WC_Lib") (part "MAX7219CWG"))
    )
  )
  (nets
    (net (code "1") (name "/CLK") (class "Default")
      (node (ref "P1") (pin "5") (pinfunction "5_5") (pintype "passive"))
      (node (ref "U1") (pin "13") (pinfunction "CLK_13") (pintype "passive"))
      (node (ref "U2") (pin "13") (pinfunction "CLK_13") (pintype "passive"))
      (node (ref "U3") (pin "13") (pinfunction "CLK_13") (pintype "passive"))
      (node (ref "U4") (pin "13") (pinfunction "CLK_13") (pintype "passive"))
    )
    (net (code "2") (name "/DIN_U1") (class "Default")
      (node (ref "P1") (pin "3") (pinfunction "3_3") (pintype "passive"))
      (node (ref "U1") (pin "1") (pinfunction "DIN_1") (pintype "passive"))
    )
    (net (code "3") (name "/DOUT_U1") (class "Default")
      (node (ref "U1") (pin "24") (pinfunction "DOUT_24") (pintype "power_in"))
      (node (ref "U2") (pin "1") (pinfunction "DIN_1") (pintype "passive"))
    )
    (net (code "4") (name "/DOUT_U2") (class "Default")
      (node (ref "U2") (pin "24") (pinfunction "DOUT_24") (pintype "power_in"))
      (node (ref "U3") (pin "1") (pinfunction "DIN_1") (pintype "passive"))
    )
    (net (code "5") (name "/DOUT_U3") (class "Default")
      (node (ref "U3") (pin "24") (pinfunction "DOUT_24") (pintype "power_in"))
      (node (ref "U4") (pin "1") (pinfunction "DIN_1") (pintype "passive"))
    )
    (net (code "6") (name "/LED0_U1") (class "Default")
      (node (ref "LED1") (pin "1") (pinfunction "1_1") (pintype "passive"))
      (node (ref "LED2") (pin "1") (pinfunction "1_1") (pintype "passive"))
      (node (ref "LED3") (pin "1") (pinfunction "1_1") (pintype "passive"))
      (node (ref "LED4") (pin "1") (pinfunction "1_1") (pintype "passive"))
      (node (ref "LED5") (pin "1") (pinfunction "1_1") (pintype "passive"))
      (node (ref "LED6") (pin "1") (pinfunction "1_1") (pintype "passive"))
      (node (ref "LED7") (pin "1") (pinfunction "1_1") (pintype "passive"))
      (node (ref "LED8") (pin "1") (pinfunction "1_1") (pintype "passive"))
      (node (ref "U1") (pin "2") (pinfunction "DIG_0_2") (pintype "passive"))
    )
    (net (code "7") (name "/LED0_U2") (class "Default")
      (node (ref "LED10") (pin "1") (pinfunction "1_1") (pintype "passive"))
      (node (ref "LED11") (pin "1") (pinfunction "1_1") (pintype "passive"))
      (node (ref "LED9") (pin "1") (pinfunction "1_1") (pintype "passive"))
      (node (ref "U2") (pin "2") (pinfunction "DIG_0_2") (pintype "passive"))
    )
    (net (code "8") (name "/LED0_U3") (class "Default")
      (node (ref "LED89") (pin "1") (pinfunction "1_1") (pintype "passive"))
      (node (ref "LED90") (pin "1") (pinfunction "1_1") (pintype "passive"))
      (node (ref "LED91") (pin "1") (pinfunction "1_1") (pintype "passive"))
      (node (ref "LED92") (pin "1") (pinfunction "1_1") (pintype "passive"))
      (node (ref "LED93") (pin "1") (pinfunction "1_1") (pintype "passive"))
      (node (ref "LED94") (pin "1") (pinfunction "1_1") (pintype "passive"))
      (node (ref "LED95") (pin "1") (pinfunction "1_1") (pintype "passive"))
      (node (ref "LED96") (pin "1") (pinfunction "1_1") (pintype "passive"))
      (node (ref "U3") (pin "2") (pinfunction "DIG_0_2") (pintype "passive"))
    )
    (net (code "9") (name "/LED0_U4") (class "Default")
      (node (ref "LED97") (pin "1") (pinfunction "1_1") (pintype "passive"))
      (node (ref "LED98") (pin "1") (pinfunction "1_1") (pintype "passive"))
      (node (ref "LED99") (pin "1") (pinfunction "1_1") (pintype "passive"))
      (node (ref "U4") (pin "2") (pinfunction "DIG_0_2") (pintype "passive"))
    )
    (net (code "10") (name "/LED1_U1") (class "Default")
      (node (ref "LED12") (pin "1") (pinfunction "1_1") (pintype "passive"))
      (node (ref "LED13") (pin "1") (pinfunction "1_1") (pintype "passive"))
      (node (ref "LED14") (pin "1") (pinfunction "1_1") (pintype "passive"))
      (node (ref "LED15") (pin "1") (pinfunction "1_1") (pintype "passive"))
      (node (ref "LED16") (pin "1") (pinfunction "1_1") (pintype "passive"))
      (node (ref "LED17") (pin "1") (pinfunction "1_1") (pintype "passive"))
      (node (ref "LED18") (pin "1") (pinfunction "1_1") (pintype "passive"))
      (node (ref "LED19") (pin "1") (pinfunction "1_1") (pintype "passive"))
      (node (ref "U1") (pin "11") (pinfunction "DIG_1_11") (pintype "passive"))
    )
    (net (code "11") (name "/LED1_U2") (class "Default")
      (node (ref "LED20") (pin "1") (pinfunction "1_1") (pintype "passive"))
      (node (ref "LED21") (pin "1") (pinfunction "1_1") (pintype "passive"))
      (node (ref "LED22") (pin "1") (pinfunction "1_1") (pintype "passive"))
      (node (ref "U2") (pin "11") (pinfunction "DIG_1_11") (pintype "passive"))
    )
    (net (code "12") (name "/LED1_U3") (class "Default")
      (node (ref "LED100") (pin "1") (pinfunction "1_1") (pintype "passive"))
      (node (ref "LED101") (pin "1") (pinfunction "1_1") (pintype "passive"))
      (node (ref "LED102") (pin "1") (pinfunction "1_1") (pintype "passive"))
      (node (ref "LED103") (pin "1") (pinfunction "1_1") (pintype "passive"))
      (node (ref "LED104") (pin "1") (pinfunction "1_1") (pintype "passive"))
      (node (ref "LED105") (pin "1") (pinfunction "1_1") (pintype "passive"))
      (node (ref "LED106") (pin "1") (pinfunction "1_1") (pintype "passive"))
      (node (ref "LED107") (pin "1") (pinfunction "1_1") (pintype "passive"))
      (node (ref "U3") (pin "11") (pinfunction "DIG_1_11") (pintype "passive"))
    )
    (net (code "13") (name "/LED1_U4") (class "Default")
      (node (ref "LED108") (pin "1") (pinfunction "1_1") (pintype "passive"))
      (node (ref "LED109") (pin "1") (pinfunction "1_1") (pintype "passive"))
      (node (ref "LED110") (pin "1") (pinfunction "1_1") (pintype "passive"))
      (node (ref "U4") (pin "11") (pinfunction "DIG_1_11") (pintype "passive"))
    )
    (net (code "14") (name "/LED2_U1") (class "Default")
      (node (ref "LED23") (pin "1") (pinfunction "1_1") (pintype "passive"))
      (node (ref "LED24") (pin "1") (pinfunction "1_1") (pintype "passive"))
      (node (ref "LED25") (pin "1") (pinfunction "1_1") (pintype "passive"))
      (node (ref "LED26") (pin "1") (pinfunction "1_1") (pintype "passive"))
      (node (ref "LED27") (pin "1") (pinfunction "1_1") (pintype "passive"))
      (node (ref "LED28") (pin "1") (pinfunction "1_1") (pintype "passive"))
      (node (ref "LED29") (pin "1") (pinfunction "1_1") (pintype "passive"))
      (node (ref "LED30") (pin "1") (pinfunction "1_1") (pintype "passive"))
      (node (ref "U1") (pin "6") (pinfunction "DIG_2_6") (pintype "passive"))
    )
    (net (code "15") (name "/LED2_U2") (class "Default")
      (node (ref "LED31") (pin "1") (pinfunction "1_1") (pintype "passive"))
      (node (ref "LED32") (pin "1") (pinfunction "1_1") (pintype "passive"))
      (node (ref "LED33") (pin "1") (pinfunction "1_1") (pintype "passive"))
      (node (ref "U2") (pin "6") (pinfunction "DIG_2_6") (pintype "passive"))
    )
    (net (code "16") (name "/LED2_U3") (class "Default")
      (node (ref "LED111") (pin "1") (pinfunction "1_1") (pintype "passive"))
      (node (ref "LED112") (pin "1") (pinfunction "1_1") (pintype "passive"))
      (node (ref "LED113") (pin "1") (pinfunction "1_1") (pintype "passive"))
      (node (ref "LED114") (pin "1") (pinfunction "1_1") (pintype "passive"))
      (node (ref "LED115") (pin "1") (pinfunction "1_1") (pintype "passive"))
      (node (ref "LED116") (pin "1") (pinfunction "1_1") (pintype "passive"))
      (node (ref "LED117") (pin "1") (pinfunction "1_1") (pintype "passive"))
      (node (ref "LED118") (pin "1") (pinfunction "1_1") (pintype "passive"))
      (node (ref "U3") (pin "6") (pinfunction "DIG_2_6") (pintype "passive"))
    )
    (net (code "17") (name "/LED2_U4") (class "Default")
      (node (ref "LED119") (pin "1") (pinfunction "1_1") (pintype "passive"))
      (node (ref "LED120") (pin "1") (pinfunction "1_1") (pintype "passive"))
      (node (ref "LED121") (pin "1") (pinfunction "1_1") (pintype "passive"))
      (node (ref "U4") (pin "6") (pinfunction "DIG_2_6") (pintype "passive"))
    )
    (net (code "18") (name "/LED3_U1") (class "Default")
      (node (ref "LED34") (pin "1") (pinfunction "1_1") (pintype "passive"))
      (node (ref "LED35") (pin "1") (pinfunction "1_1") (pintype "passive"))
      (node (ref "LED36") (pin "1") (pinfunction "1_1") (pintype "passive"))
      (node (ref "LED37") (pin "1") (pinfunction "1_1") (pintype "passive"))
      (node (ref "LED38") (pin "1") (pinfunction "1_1") (pintype "passive"))
      (node (ref "LED39") (pin "1") (pinfunction "1_1") (pintype "passive"))
      (node (ref "LED40") (pin "1") (pinfunction "1_1") (pintype "passive"))
      (node (ref "LED41") (pin "1") (pinfunction "1_1") (pintype "passive"))
      (node (ref "U1") (pin "7") (pinfunction "DIG_3_7") (pintype "passive"))
    )
    (net (code "19") (name "/LED3_U2") (class "Default")
      (node (ref "LED42") (pin "1") (pinfunction "1_1") (pintype "passive"))
      (node (ref "LED43") (pin "1") (pinfunction "1_1") (pintype "passive"))
      (node (ref "LED44") (pin "1") (pinfunction "1_1") (pintype "passive"))
      (node (ref "U2") (pin "7") (pinfunction "DIG_3_7") (pintype "passive"))
    )
    (net (code "20") (name "/LED3_U4") (class "Default")
      (node (ref "LED_M1") (pin "1") (pinfunction "1_1") (pintype "passive"))
      (node (ref "LED_M2") (pin "1") (pinfunction "1_1") (pintype "passive"))
      (node (ref "LED_M3") (pin "1") (pinfunction "1_1") (pintype "passive"))
      (node (ref "LED_M4") (pin "1") (pinfunction "1_1") (pintype "passive"))
      (node (ref "U4") (pin "7") (pinfunction "DIG_3_7") (pintype "passive"))
    )
    (net (code "21") (name "/LED4_U1") (class "Default")
      (node (ref "LED45") (pin "1") (pinfunction "1_1") (pintype "passive"))
      (node (ref "LED46") (pin "1") (pinfunction "1_1") (pintype "passive"))
      (node (ref "LED47") (pin "1") (pinfunction "1_1") (pintype "passive"))
      (node (ref "LED48") (pin "1") (pinfunction "1_1") (pintype "passive"))
      (node (ref "LED49") (pin "1") (pinfunction "1_1") (pintype "passive"))
      (node (ref "LED50") (pin "1") (pinfunction "1_1") (pintype "passive"))
      (node (ref "LED51") (pin "1") (pinfunction "1_1") (pintype "passive"))
      (node (ref "LED52") (pin "1") (pinfunction "1_1") (pintype "passive"))
      (node (ref "U1") (pin "3") (pinfunction "DIG_4_3") (pintype "passive"))
    )
    (net (code "22") (name "/LED4_U2") (class "Default")
      (node (ref "LED53") (pin "1") (pinfunction "1_1") (pintype "passive"))
      (node (ref "LED54") (pin "1") (pinfunction "1_1") (pintype "passive"))
      (node (ref "LED55") (pin "1") (pinfunction "1_1") (pintype "passive"))
      (node (ref "U2") (pin "3") (pinfunction "DIG_4_3") (pintype "passive"))
    )
    (net (code "23") (name "/LED5_U1") (class "Default")
      (node (ref "LED56") (pin "1") (pinfunction "1_1") (pintype "passive"))
      (node (ref "LED57") (pin "1") (pinfunction "1_1") (pintype "passive"))
      (node (ref "LED58") (pin "1") (pinfunction "1_1") (pintype "passive"))
      (node (ref "LED59") (pin "1") (pinfunction "1_1") (pintype "passive"))
      (node (ref "LED60") (pin "1") (pinfunction "1_1") (pintype "passive"))
      (node (ref "LED61") (pin "1") (pinfunction "1_1") (pintype "passive"))
      (node (ref "LED62") (pin "1") (pinfunction "1_1") (pintype "passive"))
      (node (ref "LED63") (pin "1") (pinfunction "1_1") (pintype "passive"))
      (node (ref "U1") (pin "10") (pinfunction "DIG_5_10") (pintype "passive"))
    )
    (net (code "24") (name "/LED5_U2") (class "Default")
      (node (ref "LED64") (pin "1") (pinfunction "1_1") (pintype "passive"))
      (node (ref "LED65") (pin "1") (pinfunction "1_1") (pintype "passive"))
      (node (ref "LED66") (pin "1") (pinfunction "1_1") (pintype "passive"))
      (node (ref "U2") (pin "10") (pinfunction "DIG_5_10") (pintype "passive"))
    )
    (net (code "25") (name "/LED6_U1") (class "Default")
      (node (ref "LED67") (pin "1") (pinfunction "1_1") (pintype "passive"))
      (node (ref "LED68") (pin "1") (pinfunction "1_1") (pintype "passive"))
      (node (ref "LED69") (pin "1") (pinfunction "1_1") (pintype "passive"))
      (node (ref "LED70") (pin "1") (pinfunction "1_1") (pintype "passive"))
      (node (ref "LED71") (pin "1") (pinfunction "1_1") (pintype "passive"))
      (node (ref "LED72") (pin "1") (pinfunction "1_1") (pintype "passive"))
      (node (ref "LED73") (pin "1") (pinfunction "1_1") (pintype "passive"))
      (node (ref "LED74") (pin "1") (pinfunction "1_1") (pintype "passive"))
      (node (ref "U1") (pin "5") (pinfunction "DIG_6_5") (pintype "passive"))
    )
    (net (code "26") (name "/LED6_U2") (class "Default")
      (node (ref "LED75") (pin "1") (pinfunction "1_1") (pintype "passive"))
      (node (ref "LED76") (pin "1") (pinfunction "1_1") (pintype "passive"))
      (node (ref "LED77") (pin "1") (pinfunction "1_1") (pintype "passive"))
      (node (ref "U2") (pin "5") (pinfunction "DIG_6_5") (pintype "passive"))
    )
    (net (code "27") (name "/LED7_U1") (class "Default")
      (node (ref "LED78") (pin "1") (pinfunction "1_1") (pintype "passive"))
      (node (ref "LED79") (pin "1") (pinfunction "1_1") (pintype "passive"))
      (node (ref "LED80") (pin "1") (pinfunction "1_1") (pintype "passive"))
      (node (ref "LED81") (pin "1") (pinfunction "1_1") (pintype "passive"))
      (node (ref "LED82") (pin "1") (pinfunction "1_1") (pintype "passive"))
      (node (ref "LED83") (pin "1") (pinfunction "1_1") (pintype "passive"))
      (node (ref "LED84") (pin "1") (pinfunction "1_1") (pintype "passive"))
      (node (ref "LED85") (pin "1") (pinfunction "1_1") (pintype "passive"))
      (node (ref "U1") (pin "8") (pinfunction "DIG_7_8") (pintype "passive"))
    )
    (net (code "28") (name "/LED7_U2") (class "Default")
      (node (ref "LED86") (pin "1") (pinfunction "1_1") (pintype "passive"))
      (node (ref "LED87") (pin "1") (pinfunction "1_1") (pintype "passive"))
      (node (ref "LED88") (pin "1") (pinfunction "1_1") (pintype "passive"))
      (node (ref "U2") (pin "8") (pinfunction "DIG_7_8") (pintype "passive"))
    )
    (net (code "29") (name "/LEDA_U1") (class "Default")
      (node (ref "LED13") (pin "2") (pinfunction "2_2") (pintype "passive"))
      (node (ref "LED2") (pin "2") (pinfunction "2_2") (pintype "passive"))
      (node (ref "LED24") (pin "2") (pinfunction "2_2") (pintype "passive"))
      (node (ref "LED35") (pin "2") (pinfunction "2_2") (pintype "passive"))
      (node (ref "LED46") (pin "2") (pinfunction "2_2") (pintype "passive"))
      (node (ref "LED57") (pin "2") (pinfunction "2_2") (pintype "passive"))
      (node (ref "LED68") (pin "2") (pinfunction "2_2") (pintype "passive"))
      (node (ref "LED79") (pin "2") (pinfunction "2_2") (pintype "passive"))
      (node (ref "U1") (pin "14") (pinfunction "SEG_A_14") (pintype "passive"))
    )
    (net (code "30") (name "/LEDA_U3") (class "Default")
      (node (ref "LED101") (pin "2") (pinfunction "2_2") (pintype "passive"))
      (node (ref "LED112") (pin "2") (pinfunction "2_2") (pintype "passive"))
      (node (ref "LED90") (pin "2") (pinfunction "2_2") (pintype "passive"))
      (node (ref "U3") (pin "14") (pinfunction "SEG_A_14") (pintype "passive"))
    )
    (net (code "31") (name "/LEDB_U1") (class "Default")
      (node (ref "LED14") (pin "2") (pinfunction "2_2") (pintype "passive"))
      (node (ref "LED25") (pin "2") (pinfunction "2_2") (pintype "passive"))
      (node (ref "LED3") (pin "2") (pinfunction "2_2") (pintype "passive"))
      (node (ref "LED36") (pin "2") (pinfunction "2_2") (pintype "passive"))
      (node (ref "LED47") (pin "2") (pinfunction "2_2") (pintype "passive"))
      (node (ref "LED58") (pin "2") (pinfunction "2_2") (pintype "passive"))
      (node (ref "LED69") (pin "2") (pinfunction "2_2") (pintype "passive"))
      (node (ref "LED80") (pin "2") (pinfunction "2_2") (pintype "passive"))
      (node (ref "U1") (pin "16") (pinfunction "SEG_B_16") (pintype "passive"))
    )
    (net (code "32") (name "/LEDB_U3") (class "Default")
      (node (ref "LED102") (pin "2") (pinfunction "2_2") (pintype "passive"))
      (node (ref "LED113") (pin "2") (pinfunction "2_2") (pintype "passive"))
      (node (ref "LED91") (pin "2") (pinfunction "2_2") (pintype "passive"))
      (node (ref "U3") (pin "16") (pinfunction "SEG_B_16") (pintype "passive"))
    )
    (net (code "33") (name "/LEDC_U1") (class "Default")
      (node (ref "LED15") (pin "2") (pinfunction "2_2") (pintype "passive"))
      (node (ref "LED26") (pin "2") (pinfunction "2_2") (pintype "passive"))
      (node (ref "LED37") (pin "2") (pinfunction "2_2") (pintype "passive"))
      (node (ref "LED4") (pin "2") (pinfunction "2_2") (pintype "passive"))
      (node (ref "LED48") (pin "2") (pinfunction "2_2") (pintype "passive"))
      (node (ref "LED59") (pin "2") (pinfunction "2_2") (pintype "passive"))
      (node (ref "LED70") (pin "2") (pinfunction "2_2") (pintype "passive"))
      (node (ref "LED81") (pin "2") (pinfunction "2_2") (pintype "passive"))
      (node (ref "U1") (pin "20") (pinfunction "SEG_C_20") (pintype "passive"))
    )
    (net (code "34") (name "/LEDC_U3") (class "Default")
      (node (ref "LED103") (pin "2") (pinfunction "2_2") (pintype "passive"))
      (node (ref "LED114") (pin "2") (pinfunction "2_2") (pintype "passive"))
      (node (ref "LED92") (pin "2") (pinfunction "2_2") (pintype "passive"))
      (node (ref "U3") (pin "20") (pinfunction "SEG_C_20") (pintype "passive"))
    )
    (net (code "35") (name "/LEDDP_U1") (class "Default")
      (node (ref "LED1") (pin "2") (pinfunction "2_2") (pintype "passive"))
      (node (ref "LED12") (pin "2") (pinfunction "2_2") (pintype "passive"))
      (node (ref "LED23") (pin "2") (pinfunction "2_2") (pintype "passive"))
      (node (ref "LED34") (pin "2") (pinfunction "2_2") (pintype "passive"))
      (node (ref "LED45") (pin "2") (pinfunction "2_2") (pintype "passive"))
      (node (ref "LED56") (pin "2") (pinfunction "2_2") (pintype "passive"))
      (node (ref "LED67") (pin "2") (pinfunction "2_2") (pintype "passive"))
      (node (ref "LED78") (pin "2") (pinfunction "2_2") (pintype "passive"))
      (node (ref "U1") (pin "22") (pinfunction "SEG_DP_22") (pintype "passive"))
    )
    (net (code "36") (name "/LEDDP_U3") (class "Default")
      (node (ref "LED100") (pin "2") (pinfunction "2_2") (pintype "passive"))
      (node (ref "LED111") (pin "2") (pinfunction "2_2") (pintype "passive"))
      (node (ref "LED89") (pin "2") (pinfunction "2_2") (pintype "passive"))
      (node (ref "U3") (pin "22") (pinfunction "SEG_DP_22") (pintype "passive"))
    )
    (net (code "37") (name "/LEDD_U1") (class "Default")
      (node (ref "LED16") (pin "2") (pinfunction "2_2") (pintype "passive"))
      (node (ref "LED27") (pin "2") (pinfunction "2_2") (pintype "passive"))
      (node (ref "LED38") (pin "2") (pinfunction "2_2") (pintype "passive"))
      (node (ref "LED49") (pin "2") (pinfunction "2_2") (pintype "passive"))
      (node (ref "LED5") (pin "2") (pinfunction "2_2") (pintype "passive"))
      (node (ref "LED60") (pin "2") (pinfunction "2_2") (pintype "passive"))
      (node (ref "LED71") (pin "2") (pinfunction "2_2") (pintype "passive"))
      (node (ref "LED82") (pin "2") (pinfunction "2_2") (pintype "passive"))
      (node (ref "U1") (pin "23") (pinfunction "SEG_D_23") (pintype "passive"))
    )
    (net (code "38") (name "/LEDD_U3") (class "Default")
      (node (ref "LED104") (pin "2") (pinfunction "2_2") (pintype "passive"))
      (node (ref "LED115") (pin "2") (pinfunction "2_2") (pintype "passive"))
      (node (ref "LED93") (pin "2") (pinfunction "2_2") (pintype "passive"))
      (node (ref "U3") (pin "23") (pinfunction "SEG_D_23") (pintype "passive"))
    )
    (net (code "39") (name "/LEDD_U4") (class "Default")
      (node (ref "LED_M1") (pin "2") (pinfunction "2_2") (pintype "passive"))
      (node (ref "U4") (pin "23") (pinfunction "SEG_D_23") (pintype "passive"))
    )
    (net (code "40") (name "/LEDE_U1") (class "Default")
      (node (ref "LED17") (pin "2") (pinfunction "2_2") (pintype "passive"))
      (node (ref "LED28") (pin "2") (pinfunction "2_2") (pintype "passive"))
      (node (ref "LED39") (pin "2") (pinfunction "2_2") (pintype "passive"))
      (node (ref "LED50") (pin "2") (pinfunction "2_2") (pintype "passive"))
      (node (ref "LED6") (pin "2") (pinfunction "2_2") (pintype "passive"))
      (node (ref "LED61") (pin "2") (pinfunction "2_2") (pintype "passive"))
      (node (ref "LED72") (pin "2") (pinfunction "2_2") (pintype "passive"))
      (node (ref "LED83") (pin "2") (pinfunction "2_2") (pintype "passive"))
      (node (ref "U1") (pin "21") (pinfunction "SEG_E_21") (pintype "passive"))
    )
    (net (code "41") (name "/LEDE_U2") (class "Default")
      (node (ref "LED20") (pin "2") (pinfunction "2_2") (pintype "passive"))
      (node (ref "LED31") (pin "2") (pinfunction "2_2") (pintype "passive"))
      (node (ref "LED42") (pin "2") (pinfunction "2_2") (pintype "passive"))
      (node (ref "LED53") (pin "2") (pinfunction "2_2") (pintype "passive"))
      (node (ref "LED64") (pin "2") (pinfunction "2_2") (pintype "passive"))
      (node (ref "LED75") (pin "2") (pinfunction "2_2") (pintype "passive"))
      (node (ref "LED86") (pin "2") (pinfunction "2_2") (pintype "passive"))
      (node (ref "LED9") (pin "2") (pinfunction "2_2") (pintype "passive"))
      (node (ref "U2") (pin "21") (pinfunction "SEG_E_21") (pintype "passive"))
    )
    (net (code "42") (name "/LEDE_U3") (class "Default")
      (node (ref "LED105") (pin "2") (pinfunction "2_2") (pintype "passive"))
      (node (ref "LED116") (pin "2") (pinfunction "2_2") (pintype "passive"))
      (node (ref "LED94") (pin "2") (pinfunction "2_2") (pintype "passive"))
      (node (ref "U3") (pin "21") (pinfunction "SEG_E_21") (pintype "passive"))
    )
    (net (code "43") (name "/LEDE_U4") (class "Default")
      (node (ref "LED108") (pin "2") (pinfunction "2_2") (pintype "passive"))
      (node (ref "LED119") (pin "2") (pinfunction "2_2") (pintype "passive"))
      (node (ref "LED97") (pin "2") (pinfunction "2_2") (pintype "passive"))
      (node (ref "LED_M2") (pin "2") (pinfunction "2_2") (pintype "passive"))
      (node (ref "U4") (pin "21") (pinfunction "SEG_E_21") (pintype "passive"))
    )
    (net (code "44") (name "/LEDF_U1") (class "Default")
      (node (ref "LED18") (pin "2") (pinfunction "2_2") (pintype "passive"))
      (node (ref "LED29") (pin "2") (pinfunction "2_2") (pintype "passive"))
      (node (ref "LED40") (pin "2") (pinfunction "2_2") (pintype "passive"))
      (node (ref "LED51") (pin "2") (pinfunction "2_2") (pintype "passive"))
      (node (ref "LED62") (pin "2") (pinfunction "2_2") (pintype "passive"))
      (node (ref "LED7") (pin "2") (pinfunction "2_2") (pintype "passive"))
      (node (ref "LED73") (pin "2") (pinfunction "2_2") (pintype "passive"))
      (node (ref "LED84") (pin "2") (pinfunction "2_2") (pintype "passive"))
      (node (ref "U1") (pin "15") (pinfunction "SEG_F_15") (pintype "passive"))
    )
    (net (code "45") (name "/LEDF_U2") (class "Default")
      (node (ref "LED10") (pin "2") (pinfunction "2_2") (pintype "passive"))
      (node (ref "LED21") (pin "2") (pinfunction "2_2") (pintype "passive"))
      (node (ref "LED32") (pin "2") (pinfunction "2_2") (pintype "passive"))
      (node (ref "LED43") (pin "2") (pinfunction "2_2") (pintype "passive"))
      (node (ref "LED54") (pin "2") (pinfunction "2_2") (pintype "passive"))
      (node (ref "LED65") (pin "2") (pinfunction "2_2") (pintype "passive"))
      (node (ref "LED76") (pin "2") (pinfunction "2_2") (pintype "passive"))
      (node (ref "LED87") (pin "2") (pinfunction "2_2") (pintype "passive"))
      (node (ref "U2") (pin "15") (pinfunction "SEG_F_15") (pintype "passive"))
    )
    (net (code "46") (name "/LEDF_U3") (class "Default")
      (node (ref "LED106") (pin "2") (pinfunction "2_2") (pintype "passive"))
      (node (ref "LED117") (pin "2") (pinfunction "2_2") (pintype "passive"))
      (node (ref "LED95") (pin "2") (pinfunction "2_2") (pintype "passive"))
      (node (ref "U3") (pin "15") (pinfunction "SEG_F_15") (pintype "passive"))
    )
    (net (code "47") (name "/LEDF_U4") (class "Default")
      (node (ref "LED109") (pin "2") (pinfunction "2_2") (pintype "passive"))
      (node (ref "LED120") (pin "2") (pinfunction "2_2") (pintype "passive"))
      (node (ref "LED98") (pin "2") (pinfunction "2_2") (pintype "passive"))
      (node (ref "LED_M3") (pin "2") (pinfunction "2_2") (pintype "passive"))
      (node (ref "U4") (pin "15") (pinfunction "SEG_F_15") (pintype "passive"))
    )
    (net (code "48") (name "/LEDG_U1") (class "Default")
      (node (ref "LED19") (pin "2") (pinfunction "2_2") (pintype "passive"))
      (node (ref "LED30") (pin "2") (pinfunction "2_2") (pintype "passive"))
      (node (ref "LED41") (pin "2") (pinfunction "2_2") (pintype "passive"))
      (node (ref "LED52") (pin "2") (pinfunction "2_2") (pintype "passive"))
      (node (ref "LED63") (pin "2") (pinfunction "2_2") (pintype "passive"))
      (node (ref "LED74") (pin "2") (pinfunction "2_2") (pintype "passive"))
      (node (ref "LED8") (pin "2") (pinfunction "2_2") (pintype "passive"))
      (node (ref "LED85") (pin "2") (pinfunction "2_2") (pintype "passive"))
      (node (ref "U1") (pin "17") (pinfunction "SEG_G_17") (pintype "passive"))
    )
    (net (code "49") (name "/LEDG_U2") (class "Default")
      (node (ref "LED11") (pin "2") (pinfunction "2_2") (pintype "passive"))
      (node (ref "LED22") (pin "2") (pinfunction "2_2") (pintype "passive"))
      (node (ref "LED33") (pin "2") (pinfunction "2_2") (pintype "passive"))
      (node (ref "LED44") (pin "2") (pinfunction "2_2") (pintype "passive"))
      (node (ref "LED55") (pin "2") (pinfunction "2_2") (pintype "passive"))
      (node (ref "LED66") (pin "2") (pinfunction "2_2") (pintype "passive"))
      (node (ref "LED77") (pin "2") (pinfunction "2_2") (pintype "passive"))
      (node (ref "LED88") (pin "2") (pinfunction "2_2") (pintype "passive"))
      (node (ref "U2") (pin "17") (pinfunction "SEG_G_17") (pintype "passive"))
    )
    (net (code "50") (name "/LEDG_U3") (class "Default")
      (node (ref "LED107") (pin "2") (pinfunction "2_2") (pintype "passive"))
      (node (ref "LED118") (pin "2") (pinfunction "2_2") (pintype "passive"))
      (node (ref "LED96") (pin "2") (pinfunction "2_2") (pintype "passive"))
      (node (ref "U3") (pin "17") (pinfunction "SEG_G_17") (pintype "passive"))
    )
    (net (code "51") (name "/LEDG_U4") (class "Default")
      (node (ref "LED110") (pin "2") (pinfunction "2_2") (pintype "passive"))
      (node (ref "LED121") (pin "2") (pinfunction "2_2") (pintype "passive"))
      (node (ref "LED99") (pin "2") (pinfunction "2_2") (pintype "passive"))
      (node (ref "LED_M4") (pin "2") (pinfunction "2_2") (pintype "passive"))
      (node (ref "U4") (pin "17") (pinfunction "SEG_G_17") (pintype "passive"))
    )
    (net (code "52") (name "/LOAD") (class "Default")
      (node (ref "P1") (pin "4") (pinfunction "4_4") (pintype "passive"))
      (node (ref "U1") (pin "12") (pinfunction "LOAD_12") (pintype "passive"))
      (node (ref "U2") (pin "12") (pinfunction "LOAD_12") (pintype "passive"))
      (node (ref "U3") (pin "12") (pinfunction "LOAD_12") (pintype "passive"))
      (node (ref "U4") (pin "12") (pinfunction "LOAD_12") (pintype "passive"))
    )
    (net (code "53") (name "GND") (class "Default")
      (node (ref "C1") (pin "1") (pinfunction "1_1") (pintype "passive"))
      (node (ref "C2") (pin "1") (pinfunction "1_1") (pintype "passive"))
      (node (ref "C3") (pin "1") (pinfunction "1_1") (pintype "passive"))
      (node (ref "C4") (pin "1") (pinfunction "1_1") (pintype "passive"))
      (node (ref "C5") (pin "1") (pinfunction "1_1") (pintype "passive"))
      (node (ref "C6") (pin "1") (pinfunction "1_1") (pintype "passive"))
      (node (ref "C7") (pin "1") (pinfunction "1_1") (pintype "passive"))
      (node (ref "C8") (pin "1") (pinfunction "1_1") (pintype "passive"))
      (node (ref "P1") (pin "1") (pinfunction "1_1") (pintype "passive"))
      (node (ref "U1") (pin "4") (pinfunction "GND_4") (pintype "power_in"))
      (node (ref "U1") (pin "9") (pinfunction "GND_2_9") (pintype "power_in"))
      (node (ref "U2") (pin "4") (pinfunction "GND_4") (pintype "power_in"))
      (node (ref "U2") (pin "9") (pinfunction "GND_2_9") (pintype "power_in"))
      (node (ref "U3") (pin "4") (pinfunction "GND_4") (pintype "power_in"))
      (node (ref "U3") (pin "9") (pinfunction "GND_2_9") (pintype "power_in"))
      (node (ref "U4") (pin "4") (pinfunction "GND_4") (pintype "power_in"))
      (node (ref "U4") (pin "9") (pinfunction "GND_2_9") (pintype "power_in"))
    )
    (net (code "54") (name "Net-(U1-ISET)") (class "Default")
      (node (ref "R1") (pin "1") (pinfunction "1_1") (pintype "passive"))
      (node (ref "U1") (pin "18") (pinfunction "ISET_18") (pintype "passive"))
    )
    (net (code "55") (name "Net-(U2-ISET)") (class "Default")
      (node (ref "R2") (pin "1") (pinfunction "1_1") (pintype "passive"))
      (node (ref "U2") (pin "18") (pinfunction "ISET_18") (pintype "passive"))
    )
    (net (code "56") (name "Net-(U3-ISET)") (class "Default")
      (node (ref "R3") (pin "1") (pinfunction "1_1") (pintype "passive"))
      (node (ref "U3") (pin "18") (pinfunction "ISET_18") (pintype "passive"))
    )
    (net (code "57") (name "Net-(U4-ISET)") (class "Default")
      (node (ref "R4") (pin "1") (pinfunction "1_1") (pintype "passive"))
      (node (ref "U4") (pin "18") (pinfunction "ISET_18") (pintype "passive"))
    )
    (net (code "58") (name "VCC") (class "Default")
      (node (ref "C1") (pin "2") (pinfunction "2_2") (pintype "passive"))
      (node (ref "C2") (pin "2") (pinfunction "2_2") (pintype "passive"))
      (node (ref "C3") (pin "2") (pinfunction "2_2") (pintype "passive"))
      (node (ref "C4") (pin "2") (pinfunction "2_2") (pintype "passive"))
      (node (ref "C5") (pin "2") (pinfunction "2_2") (pintype "passive"))
      (node (ref "C6") (pin "2") (pinfunction "2_2") (pintype "passive"))
      (node (ref "C7") (pin "2") (pinfunction "2_2") (pintype "passive"))
      (node (ref "C8") (pin "2") (pinfunction "2_2") (pintype "passive"))
      (node (ref "P1") (pin "2") (pinfunction "2_2") (pintype "passive"))
      (node (ref "R1") (pin "2") (pinfunction "2_2") (pintype "passive"))
      (node (ref "R2") (pin "2") (pinfunction "2_2") (pintype "passive"))
      (node (ref "R3") (pin "2") (pinfunction "2_2") (pintype "passive"))
      (node (ref "R4") (pin "2") (pinfunction "2_2") (pintype "passive"))
      (node (ref "U1") (pin "19") (pinfunction "Vcc_19") (pintype "power_in"))
      (node (ref "U2") (pin "19") (pinfunction "Vcc_19") (pintype "power_in"))
      (node (ref "U3") (pin "19") (pinfunction "Vcc_19") (pintype "power_in"))
      (node (ref "U4") (pin "19") (pinfunction "Vcc_19") (pintype "power_in"))
    )
    (net (code "59") (name "unconnected-(U2-SEG_A-Pad14)") (class "Default")
      (node (ref "U2") (pin "14") (pinfunction "SEG_A_14") (pintype "passive"))
    )
    (net (code "60") (name "unconnected-(U2-SEG_B-Pad16)") (class "Default")
      (node (ref "U2") (pin "16") (pinfunction "SEG_B_16") (pintype "passive"))
    )
    (net (code "61") (name "unconnected-(U2-SEG_C-Pad20)") (class "Default")
      (node (ref "U2") (pin "20") (pinfunction "SEG_C_20") (pintype "passive"))
    )
    (net (code "62") (name "unconnected-(U2-SEG_D-Pad23)") (class "Default")
      (node (ref "U2") (pin "23") (pinfunction "SEG_D_23") (pintype "passive"))
    )
    (net (code "63") (name "unconnected-(U2-SEG_DP-Pad22)") (class "Default")
      (node (ref "U2") (pin "22") (pinfunction "SEG_DP_22") (pintype "passive"))
    )
    (net (code "64") (name "unconnected-(U3-DIG_3-Pad7)") (class "Default")
      (node (ref "U3") (pin "7") (pinfunction "DIG_3_7") (pintype "passive"))
    )
    (net (code "65") (name "unconnected-(U3-DIG_4-Pad3)") (class "Default")
      (node (ref "U3") (pin "3") (pinfunction "DIG_4_3") (pintype "passive"))
    )
    (net (code "66") (name "unconnected-(U3-DIG_5-Pad10)") (class "Default")
      (node (ref "U3") (pin "10") (pinfunction "DIG_5_10") (pintype "passive"))
    )
    (net (code "67") (name "unconnected-(U3-DIG_6-Pad5)") (class "Default")
      (node (ref "U3") (pin "5") (pinfunction "DIG_6_5") (pintype "passive"))
    )
    (net (code "68") (name "unconnected-(U3-DIG_7-Pad8)") (class "Default")
      (node (ref "U3") (pin "8") (pinfunction "DIG_7_8") (pintype "passive"))
    )
    (net (code "69") (name "unconnected-(U4-DIG_4-Pad3)") (class "Default")
      (node (ref "U4") (pin "3") (pinfunction "DIG_4_3") (pintype "passive"))
    )
    (net (code "70") (name "unconnected-(U4-DIG_5-Pad10)") (class "Default")
      (node (ref "U4") (pin "10") (pinfunction "DIG_5_10") (pintype "passive"))
    )
    (net (code "71") (name "unconnected-(U4-DIG_6-Pad5)") (class "Default")
      (node (ref "U4") (pin "5") (pinfunction "DIG_6_5") (pintype "passive"))
    )
    (net (code "72") (name "unconnected-(U4-DIG_7-Pad8)") (class "Default")
      (node (ref "U4") (pin "8") (pinfunction "DIG_7_8") (pintype "passive"))
    )
    (net (code "73") (name "unconnected-(U4-DOUT-Pad24)") (class "Default")
      (node (ref "U4") (pin "24") (pinfunction "DOUT_24") (pintype "power_in"))
    )
    (net (code "74") (name "unconnected-(U4-SEG_A-Pad14)") (class "Default")
      (node (ref "U4") (pin "14") (pinfunction "SEG_A_14") (pintype "passive"))
    )
    (net (code "75") (name "unconnected-(U4-SEG_B-Pad16)") (class "Default")
      (node (ref "U4") (pin "16") (pinfunction "SEG_B_16") (pintype "passive"))
    )
    (net (code "76") (name "unconnected-(U4-SEG_C-Pad20)") (class "Default")
      (node (ref "U4") (pin "20") (pinfunction "SEG_C_20") (pintype "passive"))
    )
    (net (code "77") (name "unconnected-(U4-SEG_DP-Pad22)") (class "Default")
      (node (ref "U4") (pin "22") (pinfunction "SEG_DP_22") (pintype "passive"))
    )
  )
)
